# key.net
KiCad netlist of a schematic drawn in Altium Designer
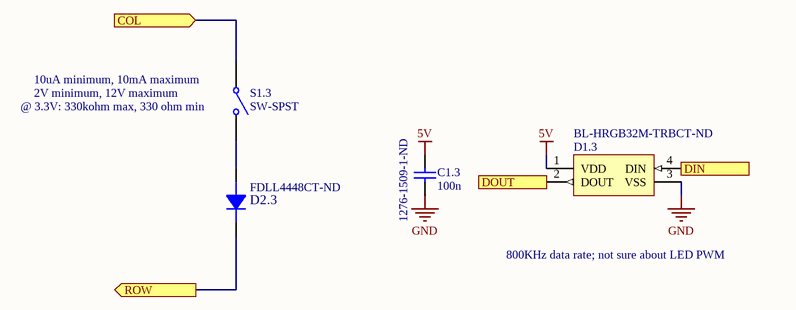
[diagram p0: key.SchDoc]

(export (version "E")
  (design (tool "Eeschema 10.0.6"))
  (components
    (comp (ref "C1.3")
      (value "100n")
      (footprint "0402")
      (fields (field (name "SUPPLIER PART NUMBER 1") "1276-1509-1-ND"))
      (libsource (lib "Luminaire") (part "CAPACITOR NON_POL"))
    )
    (comp (ref "D1.3")
      (value "Addressable RGB LED")
      (footprint "BL-HRGB32M-TRB")
      (fields (field (name "SUPPLIER PART NUMBER 1") "BL-HRGB32M-TRBCT-ND"))
      (libsource (lib "pokey") (part "BL-HRGB32M-TRB"))
    )
    (comp (ref "D2.3")
      (value "~")
      (footprint "SOD-80")
      (fields (field (name "SUPPLIER PART NUMBER 1") "FDLL4448CT-ND"))
      (libsource (lib "pokey") (part "DIODE"))
    )
    (comp (ref "S1.3")
      (value "SW-SPST")
      (footprint "PG1350")
      (description "Single-Pole, Single-Throw Switch")
      (fields (field (name "MANUFACTURER") "Kailh") (field (name "MANUFACTURER PART NUMBER") "PG1350"))
      (libsource (lib "Miscellaneous Devices") (part "SW-SPST"))
    )
  )
  (nets
    (net (code "1") (name "/COL") (class "Default")
      (node (ref "S1.3") (pin "1") (pinfunction "COMMON_1") (pintype "passive"))
    )
    (net (code "3") (name "/DIN") (class "Default")
      (node (ref "D1.3") (pin "4") (pinfunction "DIN_4") (pintype "input"))
    )
    (net (code "4") (name "/DOUT") (class "Default")
      (node (ref "D1.3") (pin "2") (pinfunction "DOUT_2") (pintype "output"))
    )
    (net (code "5") (name "/ROW") (class "Default")
      (node (ref "D2.3") (pin "K") (pinfunction "K_K") (pintype "passive"))
    )
    (net (code "6") (name "5V") (class "Default")
      (node (ref "C1.3") (pin "1") (pinfunction "1_1") (pintype "passive"))
      (node (ref "D1.3") (pin "1") (pinfunction "VDD_1") (pintype "power_in"))
    )
    (net (code "7") (name "GND") (class "Default")
      (node (ref "C1.3") (pin "2") (pinfunction "2_2") (pintype "passive"))
      (node (ref "D1.3") (pin "3") (pinfunction "VSS_3") (pintype "power_in"))
    )
    (net (code "8") (name "Net-(S1.3-NO)") (class "Default")
      (node (ref "D2.3") (pin "A") (pinfunction "A_A") (pintype "passive"))
      (node (ref "S1.3") (pin "2") (pinfunction "NO_2") (pintype "passive"))
    )
  )
)
